# pedalier.net
KiCad netlist of a schematic drawn in EAGLE
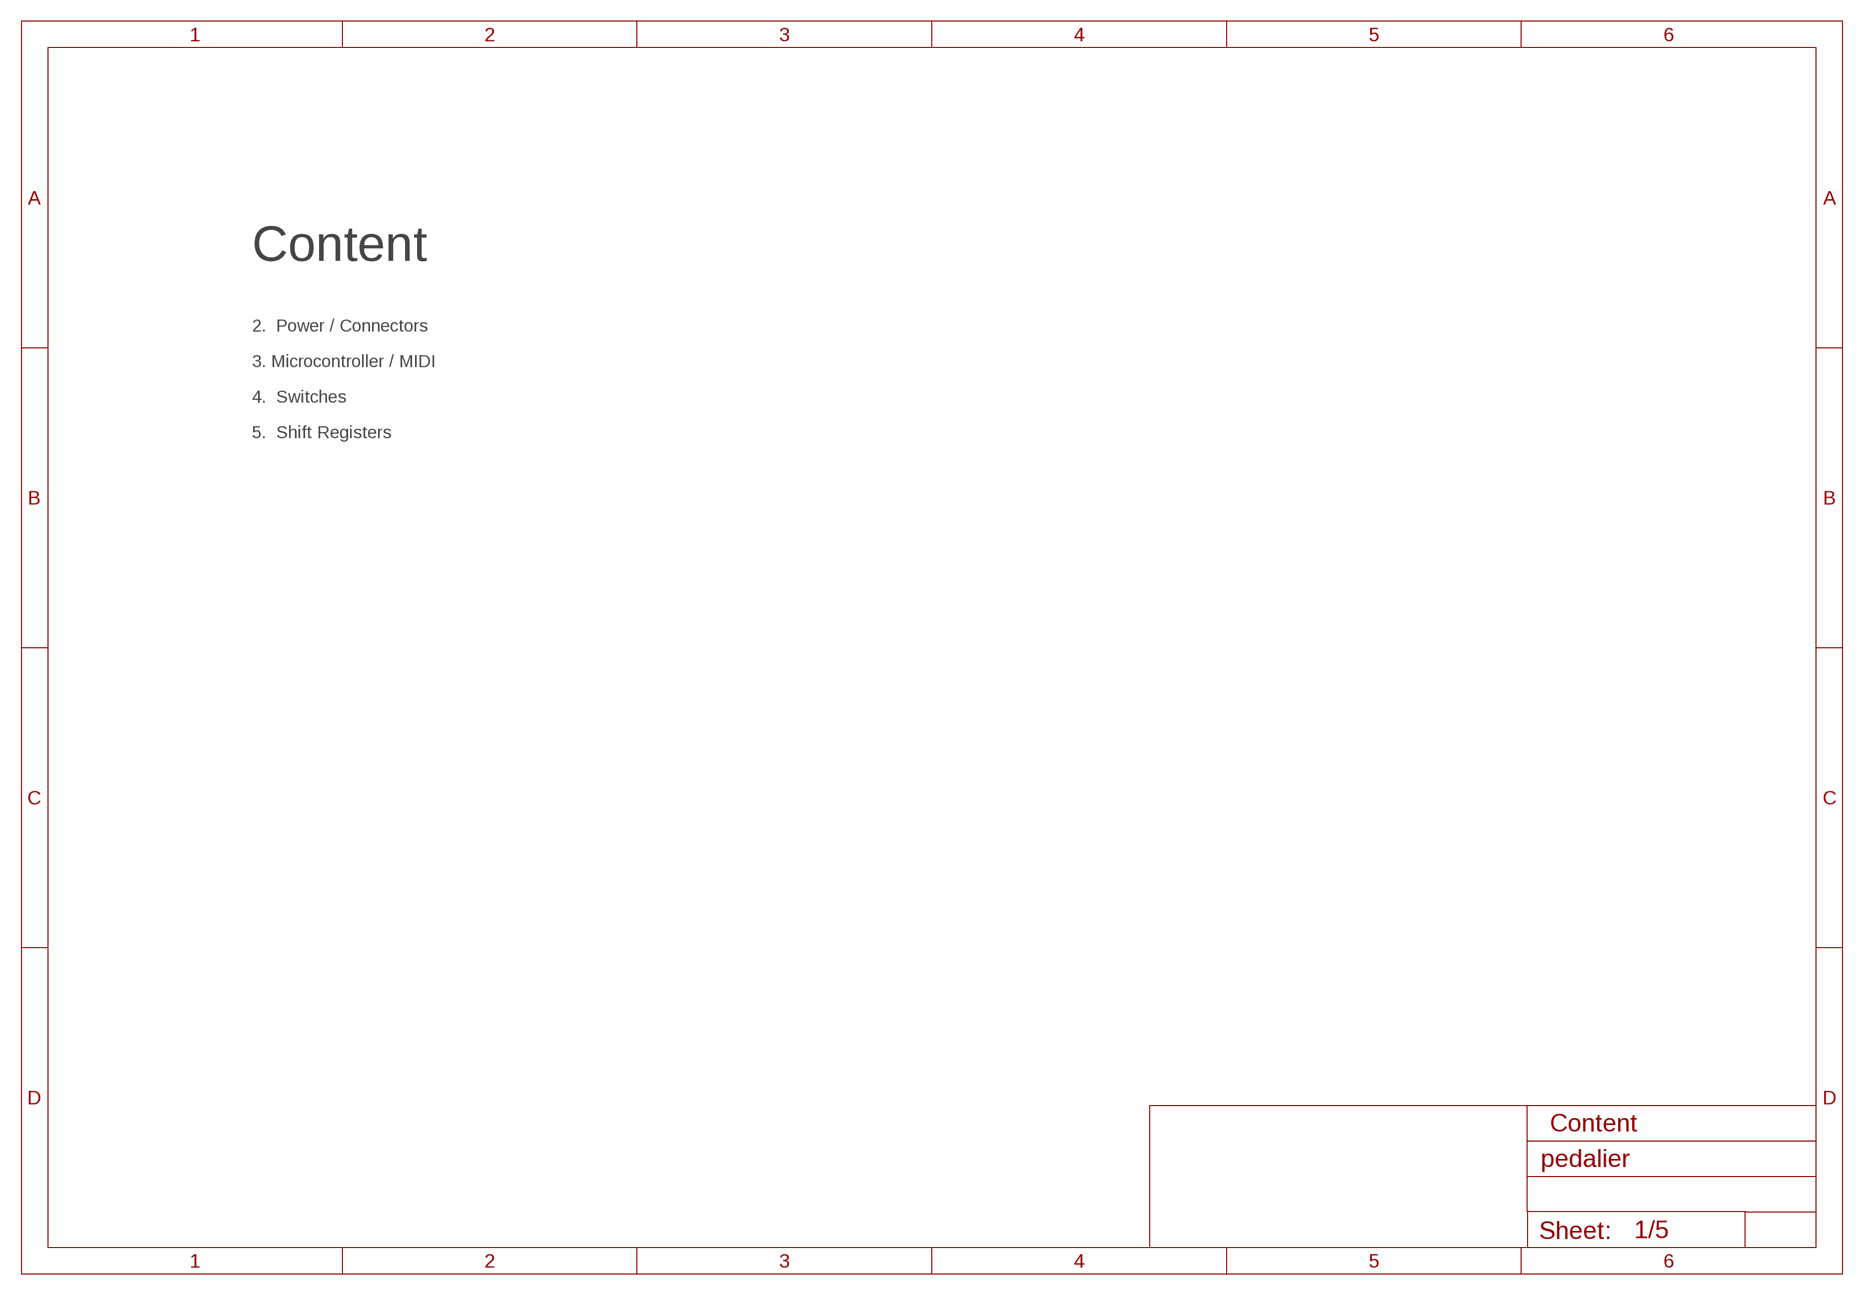
[diagram p0: schematic, sheet 1]
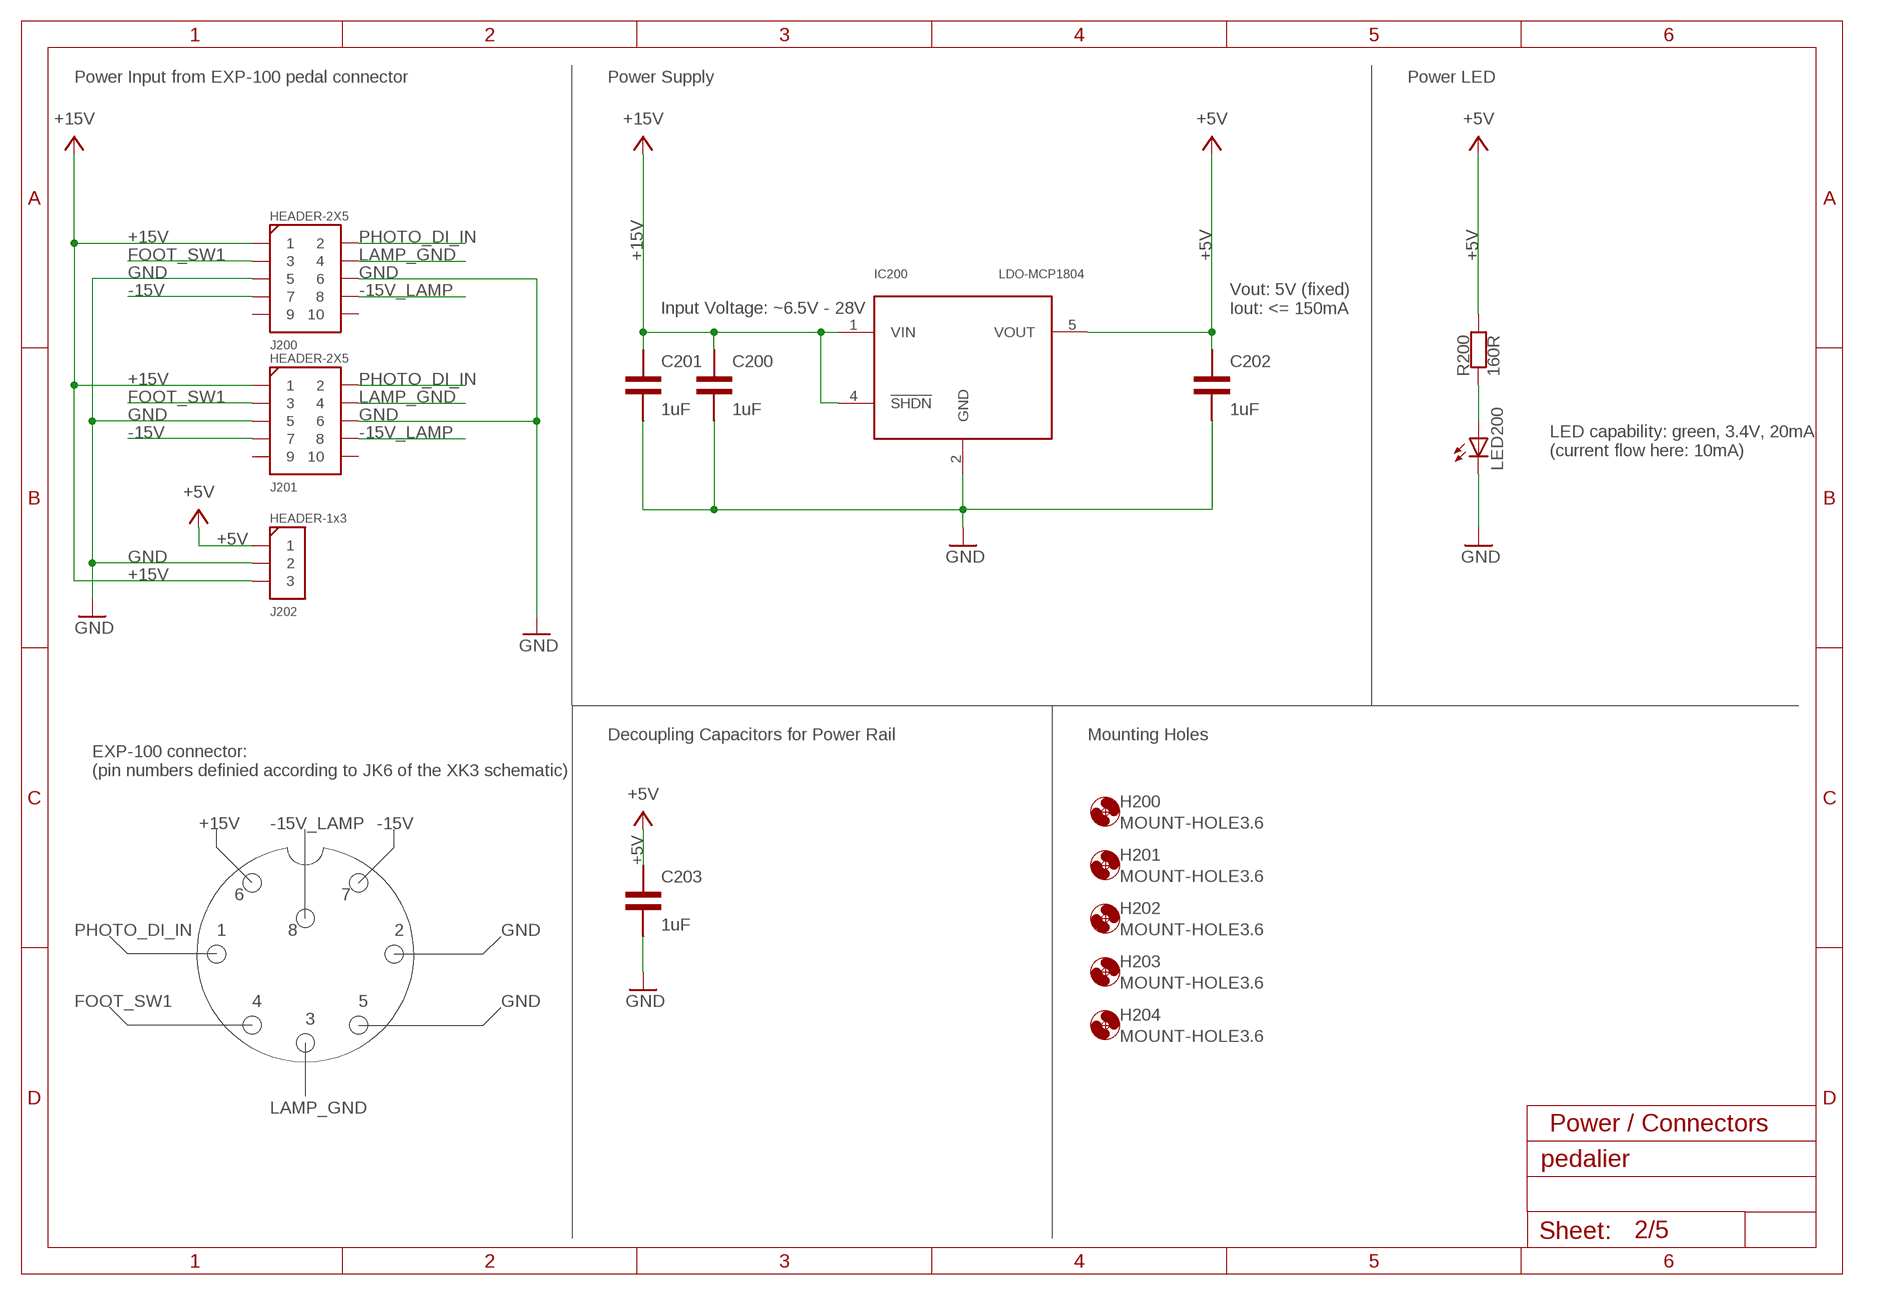
[diagram p1: schematic, sheet 2]
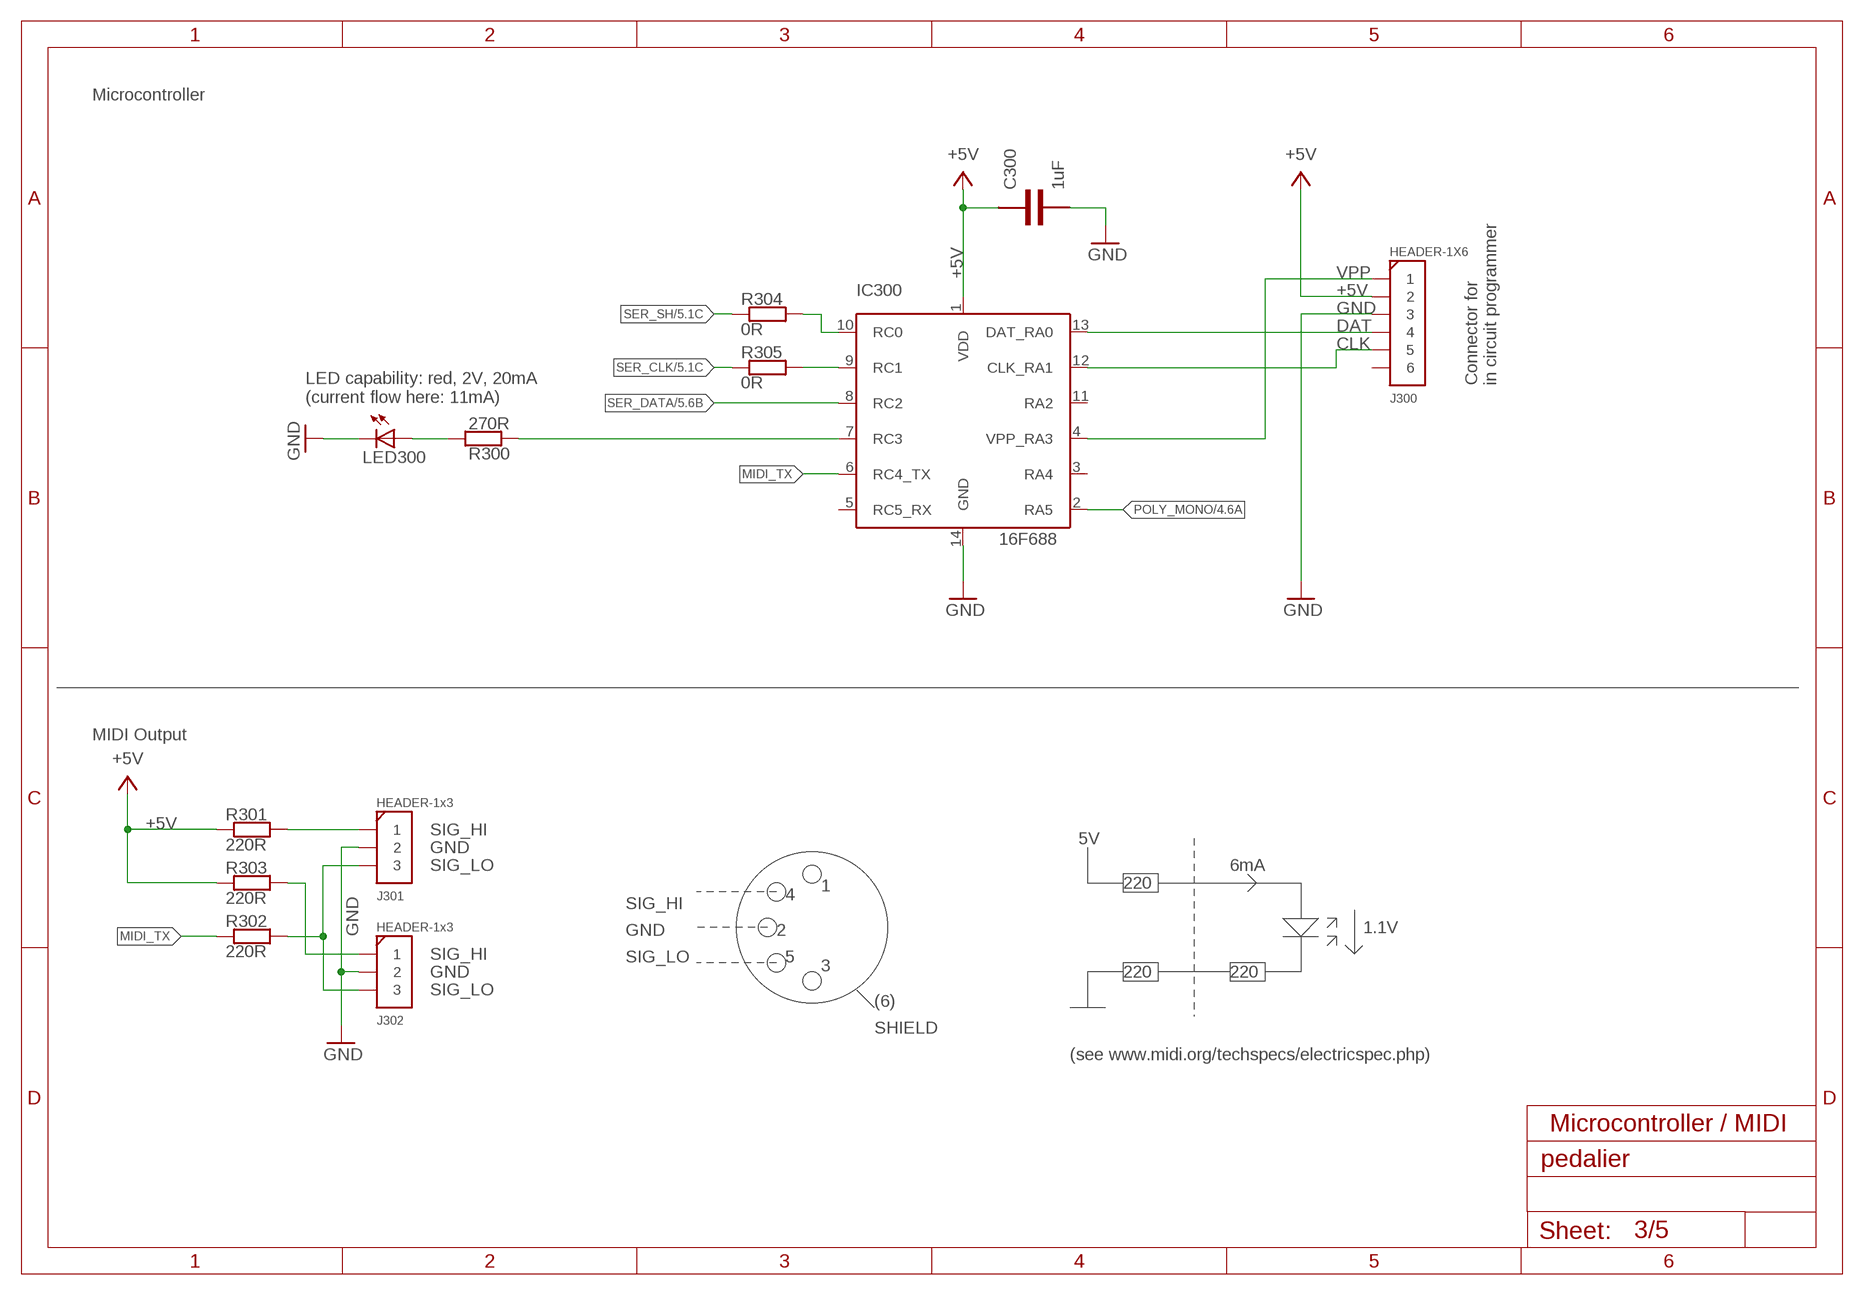
[diagram p2: schematic, sheet 3]
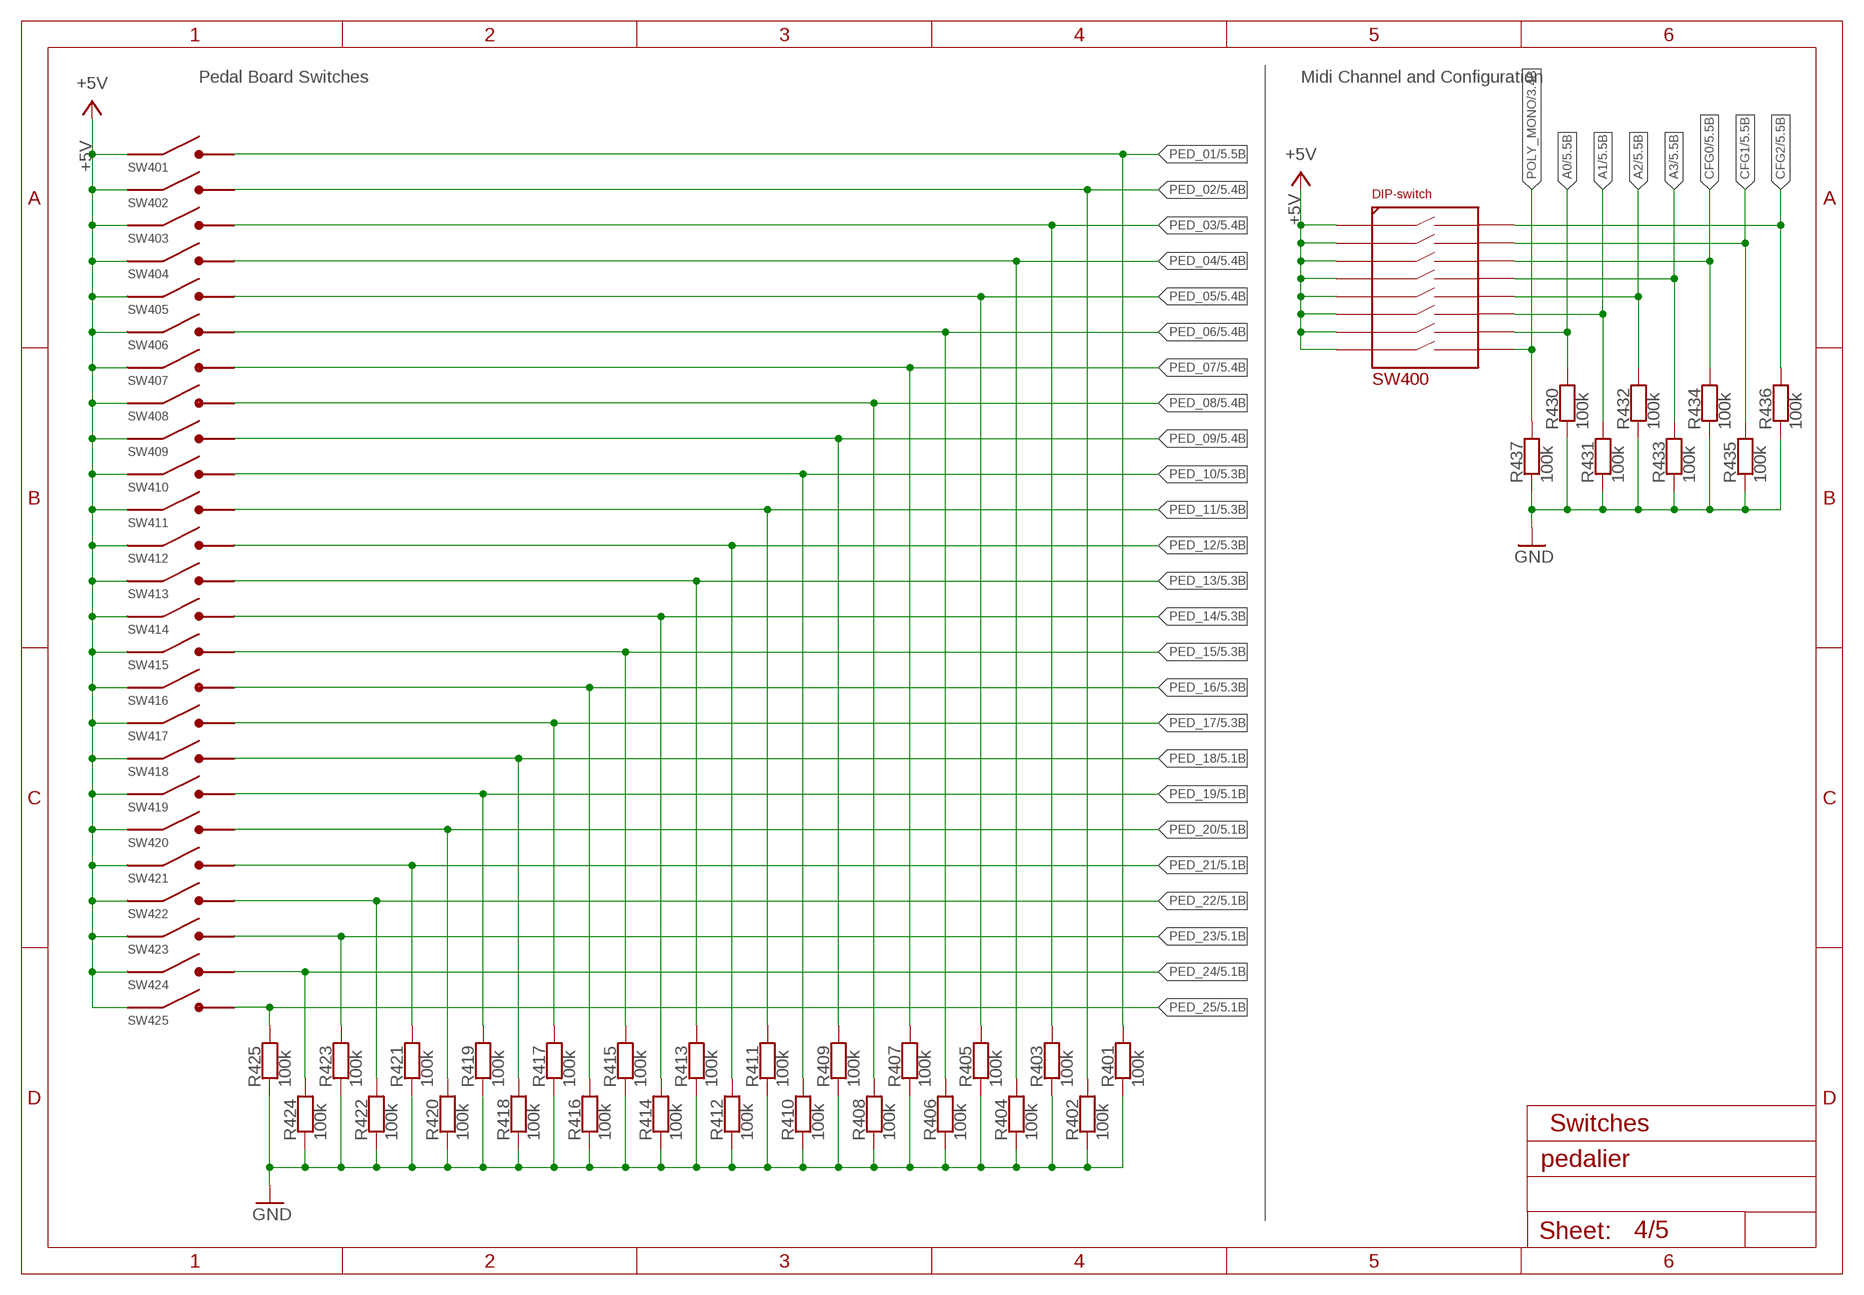
[diagram p3: schematic, sheet 4]
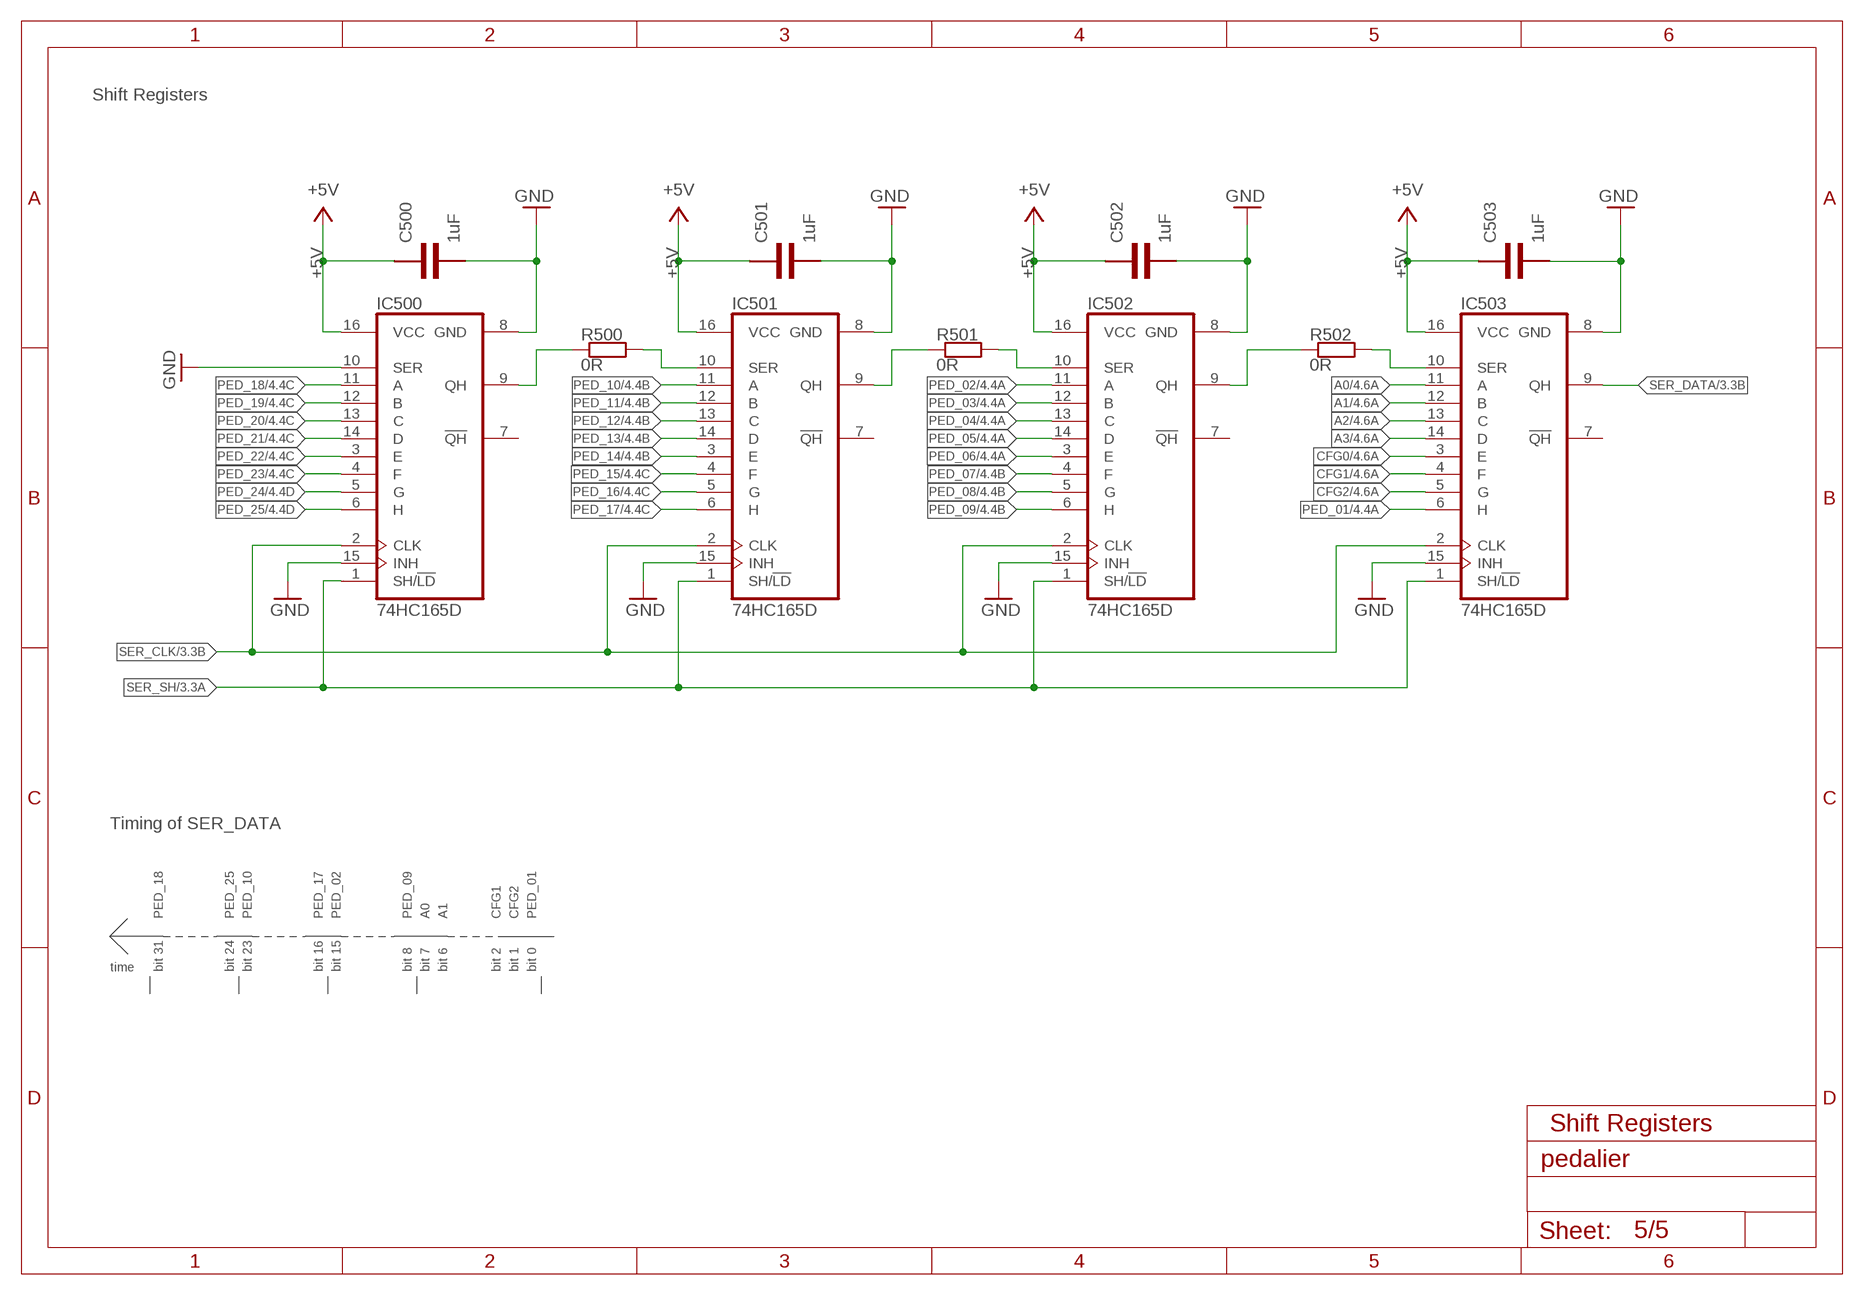
[diagram p4: schematic, sheet 5]

(export (version "E")
  (design (tool "Eeschema 10.0.6"))
  (components
    (comp (ref "R401")
      (value "100k")
      (footprint "eagle-import:R1206")
      (libsource (lib "eagle-import") (part "R"))
    )
    (comp (ref "R402")
      (value "100k")
      (footprint "eagle-import:R1206")
      (libsource (lib "eagle-import") (part "R"))
    )
    (comp (ref "R403")
      (value "100k")
      (footprint "eagle-import:R1206")
      (libsource (lib "eagle-import") (part "R"))
    )
    (comp (ref "R404")
      (value "100k")
      (footprint "eagle-import:R1206")
      (libsource (lib "eagle-import") (part "R"))
    )
    (comp (ref "R405")
      (value "100k")
      (footprint "eagle-import:R1206")
      (libsource (lib "eagle-import") (part "R"))
    )
    (comp (ref "R406")
      (value "100k")
      (footprint "eagle-import:R1206")
      (libsource (lib "eagle-import") (part "R"))
    )
    (comp (ref "R407")
      (value "100k")
      (footprint "eagle-import:R1206")
      (libsource (lib "eagle-import") (part "R"))
    )
    (comp (ref "R408")
      (value "100k")
      (footprint "eagle-import:R1206")
      (libsource (lib "eagle-import") (part "R"))
    )
    (comp (ref "R409")
      (value "100k")
      (footprint "eagle-import:R1206")
      (libsource (lib "eagle-import") (part "R"))
    )
    (comp (ref "R410")
      (value "100k")
      (footprint "eagle-import:R1206")
      (libsource (lib "eagle-import") (part "R"))
    )
    (comp (ref "R411")
      (value "100k")
      (footprint "eagle-import:R1206")
      (libsource (lib "eagle-import") (part "R"))
    )
    (comp (ref "R412")
      (value "100k")
      (footprint "eagle-import:R1206")
      (libsource (lib "eagle-import") (part "R"))
    )
    (comp (ref "R413")
      (value "100k")
      (footprint "eagle-import:R1206")
      (libsource (lib "eagle-import") (part "R"))
    )
    (comp (ref "R414")
      (value "100k")
      (footprint "eagle-import:R1206")
      (libsource (lib "eagle-import") (part "R"))
    )
    (comp (ref "R415")
      (value "100k")
      (footprint "eagle-import:R1206")
      (libsource (lib "eagle-import") (part "R"))
    )
    (comp (ref "R416")
      (value "100k")
      (footprint "eagle-import:R1206")
      (libsource (lib "eagle-import") (part "R"))
    )
    (comp (ref "R417")
      (value "100k")
      (footprint "eagle-import:R1206")
      (libsource (lib "eagle-import") (part "R"))
    )
    (comp (ref "R418")
      (value "100k")
      (footprint "eagle-import:R1206")
      (libsource (lib "eagle-import") (part "R"))
    )
    (comp (ref "R419")
      (value "100k")
      (footprint "eagle-import:R1206")
      (libsource (lib "eagle-import") (part "R"))
    )
    (comp (ref "R420")
      (value "100k")
      (footprint "eagle-import:R1206")
      (libsource (lib "eagle-import") (part "R"))
    )
    (comp (ref "R421")
      (value "100k")
      (footprint "eagle-import:R1206")
      (libsource (lib "eagle-import") (part "R"))
    )
    (comp (ref "R422")
      (value "100k")
      (footprint "eagle-import:R1206")
      (libsource (lib "eagle-import") (part "R"))
    )
    (comp (ref "R423")
      (value "100k")
      (footprint "eagle-import:R1206")
      (libsource (lib "eagle-import") (part "R"))
    )
    (comp (ref "R424")
      (value "100k")
      (footprint "eagle-import:R1206")
      (libsource (lib "eagle-import") (part "R"))
    )
    (comp (ref "R425")
      (value "100k")
      (footprint "eagle-import:R1206")
      (libsource (lib "eagle-import") (part "R"))
    )
    (comp (ref "R430")
      (value "100k")
      (footprint "eagle-import:R1206")
      (libsource (lib "eagle-import") (part "R"))
    )
    (comp (ref "R431")
      (value "100k")
      (footprint "eagle-import:R1206")
      (libsource (lib "eagle-import") (part "R"))
    )
    (comp (ref "R432")
      (value "100k")
      (footprint "eagle-import:R1206")
      (libsource (lib "eagle-import") (part "R"))
    )
    (comp (ref "R433")
      (value "100k")
      (footprint "eagle-import:R1206")
      (libsource (lib "eagle-import") (part "R"))
    )
    (comp (ref "R434")
      (value "100k")
      (footprint "eagle-import:R1206")
      (libsource (lib "eagle-import") (part "R"))
    )
    (comp (ref "R435")
      (value "100k")
      (footprint "eagle-import:R1206")
      (libsource (lib "eagle-import") (part "R"))
    )
    (comp (ref "R436")
      (value "100k")
      (footprint "eagle-import:R1206")
      (libsource (lib "eagle-import") (part "R"))
    )
    (comp (ref "R437")
      (value "100k")
      (footprint "eagle-import:R1206")
      (libsource (lib "eagle-import") (part "R"))
    )
    (comp (ref "SW400")
      (value "DIP-SW-8X")
      (footprint "eagle-import:DIP-SW-8X-GULLWING")
      (libsource (lib "eagle-import") (part "DIP-SW-8X"))
    )
    (comp (ref "SW401")
      (value "REED-SW")
      (footprint "eagle-import:KSK-1A35-SMD")
      (libsource (lib "eagle-import") (part "REED-SW"))
    )
    (comp (ref "SW402")
      (value "REED-SW")
      (footprint "eagle-import:KSK-1A35-SMD")
      (libsource (lib "eagle-import") (part "REED-SW"))
    )
    (comp (ref "SW403")
      (value "REED-SW")
      (footprint "eagle-import:KSK-1A35-SMD")
      (libsource (lib "eagle-import") (part "REED-SW"))
    )
    (comp (ref "SW404")
      (value "REED-SW")
      (footprint "eagle-import:KSK-1A35-SMD")
      (libsource (lib "eagle-import") (part "REED-SW"))
    )
    (comp (ref "SW405")
      (value "REED-SW")
      (footprint "eagle-import:KSK-1A35-SMD")
      (libsource (lib "eagle-import") (part "REED-SW"))
    )
    (comp (ref "SW406")
      (value "REED-SW")
      (footprint "eagle-import:KSK-1A35-SMD")
      (libsource (lib "eagle-import") (part "REED-SW"))
    )
    (comp (ref "SW407")
      (value "REED-SW")
      (footprint "eagle-import:KSK-1A35-SMD")
      (libsource (lib "eagle-import") (part "REED-SW"))
    )
    (comp (ref "SW408")
      (value "REED-SW")
      (footprint "eagle-import:KSK-1A35-SMD")
      (libsource (lib "eagle-import") (part "REED-SW"))
    )
    (comp (ref "SW409")
      (value "REED-SW")
      (footprint "eagle-import:KSK-1A35-SMD")
      (libsource (lib "eagle-import") (part "REED-SW"))
    )
    (comp (ref "SW410")
      (value "REED-SW")
      (footprint "eagle-import:KSK-1A35-SMD")
      (libsource (lib "eagle-import") (part "REED-SW"))
    )
    (comp (ref "SW411")
      (value "REED-SW")
      (footprint "eagle-import:KSK-1A35-SMD")
      (libsource (lib "eagle-import") (part "REED-SW"))
    )
    (comp (ref "SW412")
      (value "REED-SW")
      (footprint "eagle-import:KSK-1A35-SMD")
      (libsource (lib "eagle-import") (part "REED-SW"))
    )
    (comp (ref "SW413")
      (value "REED-SW")
      (footprint "eagle-import:KSK-1A35-SMD")
      (libsource (lib "eagle-import") (part "REED-SW"))
    )
    (comp (ref "SW414")
      (value "REED-SW")
      (footprint "eagle-import:KSK-1A35-SMD")
      (libsource (lib "eagle-import") (part "REED-SW"))
    )
    (comp (ref "SW415")
      (value "REED-SW")
      (footprint "eagle-import:KSK-1A35-SMD")
      (libsource (lib "eagle-import") (part "REED-SW"))
    )
    (comp (ref "SW416")
      (value "REED-SW")
      (footprint "eagle-import:KSK-1A35-SMD")
      (libsource (lib "eagle-import") (part "REED-SW"))
    )
    (comp (ref "SW417")
      (value "REED-SW")
      (footprint "eagle-import:KSK-1A35-SMD")
      (libsource (lib "eagle-import") (part "REED-SW"))
    )
    (comp (ref "SW418")
      (value "REED-SW")
      (footprint "eagle-import:KSK-1A35-SMD")
      (libsource (lib "eagle-import") (part "REED-SW"))
    )
    (comp (ref "SW419")
      (value "REED-SW")
      (footprint "eagle-import:KSK-1A35-SMD")
      (libsource (lib "eagle-import") (part "REED-SW"))
    )
    (comp (ref "SW420")
      (value "REED-SW")
      (footprint "eagle-import:KSK-1A35-SMD")
      (libsource (lib "eagle-import") (part "REED-SW"))
    )
    (comp (ref "SW421")
      (value "REED-SW")
      (footprint "eagle-import:KSK-1A35-SMD")
      (libsource (lib "eagle-import") (part "REED-SW"))
    )
    (comp (ref "SW422")
      (value "REED-SW")
      (footprint "eagle-import:KSK-1A35-SMD")
      (libsource (lib "eagle-import") (part "REED-SW"))
    )
    (comp (ref "SW423")
      (value "REED-SW")
      (footprint "eagle-import:KSK-1A35-SMD")
      (libsource (lib "eagle-import") (part "REED-SW"))
    )
    (comp (ref "SW424")
      (value "REED-SW")
      (footprint "eagle-import:KSK-1A35-SMD")
      (libsource (lib "eagle-import") (part "REED-SW"))
    )
    (comp (ref "SW425")
      (value "REED-SW")
      (footprint "eagle-import:KSK-1A35-SMD")
      (libsource (lib "eagle-import") (part "REED-SW"))
    )
    (comp (ref "C200")
      (value "1uF")
      (footprint "eagle-import:C1206")
      (libsource (lib "eagle-import") (part "C"))
    )
    (comp (ref "C201")
      (value "1uF")
      (footprint "eagle-import:C1206")
      (libsource (lib "eagle-import") (part "C"))
    )
    (comp (ref "C202")
      (value "1uF")
      (footprint "eagle-import:C1206")
      (libsource (lib "eagle-import") (part "C"))
    )
    (comp (ref "C203")
      (value "1uF")
      (footprint "eagle-import:C1206")
      (libsource (lib "eagle-import") (part "C"))
    )
    (comp (ref "H200")
      (value "MOUNT-HOLE3.6")
      (footprint "eagle-import:3,6")
      (libsource (lib "eagle-import") (part "MOUNT-HOLE3.6"))
    )
    (comp (ref "H201")
      (value "MOUNT-HOLE3.6")
      (footprint "eagle-import:3,6")
      (libsource (lib "eagle-import") (part "MOUNT-HOLE3.6"))
    )
    (comp (ref "H202")
      (value "MOUNT-HOLE3.6")
      (footprint "eagle-import:3,6")
      (libsource (lib "eagle-import") (part "MOUNT-HOLE3.6"))
    )
    (comp (ref "H203")
      (value "MOUNT-HOLE3.6")
      (footprint "eagle-import:3,6")
      (libsource (lib "eagle-import") (part "MOUNT-HOLE3.6"))
    )
    (comp (ref "H204")
      (value "MOUNT-HOLE3.6")
      (footprint "eagle-import:3,6")
      (libsource (lib "eagle-import") (part "MOUNT-HOLE3.6"))
    )
    (comp (ref "IC200")
      (value "LDO-MCP1804")
      (footprint "eagle-import:SOT23-5")
      (libsource (lib "eagle-import") (part "LDO-MCP1804"))
    )
    (comp (ref "J200")
      (value "HEADER-2X5")
      (footprint "eagle-import:HEADER-2X5")
      (libsource (lib "eagle-import") (part "HEADER-2X5"))
    )
    (comp (ref "J201")
      (value "HEADER-2X5")
      (footprint "eagle-import:HEADER-2X5")
      (libsource (lib "eagle-import") (part "HEADER-2X5"))
    )
    (comp (ref "J202")
      (value "HEADER-1X3")
      (footprint "eagle-import:HEADER-1X3")
      (libsource (lib "eagle-import") (part "HEADER-1X3"))
    )
    (comp (ref "LED200")
      (value "LED-BRIGHTEK")
      (footprint "eagle-import:LED1206")
      (libsource (lib "eagle-import") (part "LED-BRIGHTEK"))
    )
    (comp (ref "R200")
      (value "160R")
      (footprint "eagle-import:R1206")
      (libsource (lib "eagle-import") (part "R"))
    )
    (comp (ref "C300")
      (value "1uF")
      (footprint "eagle-import:C1206")
      (libsource (lib "eagle-import") (part "C"))
    )
    (comp (ref "IC300")
      (value "PIC16F688SOIC14")
      (footprint "eagle-import:SO14")
      (libsource (lib "eagle-import") (part "PIC16F688SOIC14"))
    )
    (comp (ref "J300")
      (value "HEADER-1X6")
      (footprint "eagle-import:HEADER-1X6")
      (libsource (lib "eagle-import") (part "HEADER-1X6"))
    )
    (comp (ref "J301")
      (value "HEADER-1X3")
      (footprint "eagle-import:HEADER-1X3")
      (libsource (lib "eagle-import") (part "HEADER-1X3"))
    )
    (comp (ref "J302")
      (value "HEADER-1X3")
      (footprint "eagle-import:HEADER-1X3")
      (libsource (lib "eagle-import") (part "HEADER-1X3"))
    )
    (comp (ref "LED300")
      (value "LED-BRIGHTEK")
      (footprint "eagle-import:LED1206")
      (libsource (lib "eagle-import") (part "LED-BRIGHTEK"))
    )
    (comp (ref "R300")
      (value "270R")
      (footprint "eagle-import:R1206")
      (libsource (lib "eagle-import") (part "R"))
    )
    (comp (ref "R301")
      (value "220R")
      (footprint "eagle-import:R1206")
      (libsource (lib "eagle-import") (part "R"))
    )
    (comp (ref "R302")
      (value "220R")
      (footprint "eagle-import:R1206")
      (libsource (lib "eagle-import") (part "R"))
    )
    (comp (ref "R303")
      (value "220R")
      (footprint "eagle-import:R1206")
      (libsource (lib "eagle-import") (part "R"))
    )
    (comp (ref "R304")
      (value "0R")
      (footprint "eagle-import:R1206")
      (libsource (lib "eagle-import") (part "R"))
    )
    (comp (ref "R305")
      (value "0R")
      (footprint "eagle-import:R1206")
      (libsource (lib "eagle-import") (part "R"))
    )
    (comp (ref "C500")
      (value "1uF")
      (footprint "eagle-import:C1206")
      (libsource (lib "eagle-import") (part "C"))
    )
    (comp (ref "C501")
      (value "1uF")
      (footprint "eagle-import:C1206")
      (libsource (lib "eagle-import") (part "C"))
    )
    (comp (ref "C502")
      (value "1uF")
      (footprint "eagle-import:C1206")
      (libsource (lib "eagle-import") (part "C"))
    )
    (comp (ref "C503")
      (value "1uF")
      (footprint "eagle-import:C1206")
      (libsource (lib "eagle-import") (part "C"))
    )
    (comp (ref "IC500")
      (value "74HC165D")
      (footprint "eagle-import:SO16")
      (libsource (lib "eagle-import") (part "74HC165D"))
    )
    (comp (ref "IC501")
      (value "74HC165D")
      (footprint "eagle-import:SO16")
      (libsource (lib "eagle-import") (part "74HC165D"))
    )
    (comp (ref "IC502")
      (value "74HC165D")
      (footprint "eagle-import:SO16")
      (libsource (lib "eagle-import") (part "74HC165D"))
    )
    (comp (ref "IC503")
      (value "74HC165D")
      (footprint "eagle-import:SO16")
      (libsource (lib "eagle-import") (part "74HC165D"))
    )
    (comp (ref "R500")
      (value "0R")
      (footprint "eagle-import:R1206")
      (libsource (lib "eagle-import") (part "R"))
    )
    (comp (ref "R501")
      (value "0R")
      (footprint "eagle-import:R1206")
      (libsource (lib "eagle-import") (part "R"))
    )
    (comp (ref "R502")
      (value "0R")
      (footprint "eagle-import:R1206")
      (libsource (lib "eagle-import") (part "R"))
    )
  )
  (nets
    (net (code "1") (name "+5V") (class "Default")
      (node (ref "C202") (pin "1") (pinfunction "P$1_1") (pintype "bidirectional"))
      (node (ref "C203") (pin "1") (pinfunction "P$1_1") (pintype "bidirectional"))
      (node (ref "C300") (pin "1") (pinfunction "P$1_1") (pintype "bidirectional"))
      (node (ref "C500") (pin "1") (pinfunction "P$1_1") (pintype "bidirectional"))
      (node (ref "C501") (pin "1") (pinfunction "P$1_1") (pintype "bidirectional"))
      (node (ref "C502") (pin "1") (pinfunction "P$1_1") (pintype "bidirectional"))
      (node (ref "C503") (pin "1") (pinfunction "P$1_1") (pintype "bidirectional"))
      (node (ref "IC200") (pin "5") (pinfunction "VOUT_5") (pintype "bidirectional"))
      (node (ref "IC300") (pin "1") (pinfunction "VDD_1") (pintype "passive"))
      (node (ref "IC500") (pin "16") (pinfunction "VCC_16") (pintype "bidirectional"))
      (node (ref "IC501") (pin "16") (pinfunction "VCC_16") (pintype "bidirectional"))
      (node (ref "IC502") (pin "16") (pinfunction "VCC_16") (pintype "bidirectional"))
      (node (ref "IC503") (pin "16") (pinfunction "VCC_16") (pintype "bidirectional"))
      (node (ref "J202") (pin "P$1") (pinfunction "1_P$1") (pintype "bidirectional"))
      (node (ref "J300") (pin "P$2") (pinfunction "2_P$2") (pintype "bidirectional"))
      (node (ref "R200") (pin "2") (pinfunction "P$2_2") (pintype "bidirectional"))
      (node (ref "R301") (pin "1") (pinfunction "P$1_1") (pintype "bidirectional"))
      (node (ref "R303") (pin "1") (pinfunction "P$1_1") (pintype "bidirectional"))
      (node (ref "SW400") (pin "P$1") (pinfunction "P$1_P$1") (pintype "bidirectional"))
      (node (ref "SW400") (pin "P$11") (pinfunction "P$11_P$11") (pintype "bidirectional"))
      (node (ref "SW400") (pin "P$13") (pinfunction "P$13_P$13") (pintype "bidirectional"))
      (node (ref "SW400") (pin "P$15") (pinfunction "P$15_P$15") (pintype "bidirectional"))
      (node (ref "SW400") (pin "P$3") (pinfunction "P$3_P$3") (pintype "bidirectional"))
      (node (ref "SW400") (pin "P$5") (pinfunction "P$5_P$5") (pintype "bidirectional"))
      (node (ref "SW400") (pin "P$7") (pinfunction "P$7_P$7") (pintype "bidirectional"))
      (node (ref "SW400") (pin "P$9") (pinfunction "P$9_P$9") (pintype "bidirectional"))
      (node (ref "SW401") (pin "1") (pinfunction "1_1") (pintype "bidirectional"))
      (node (ref "SW402") (pin "1") (pinfunction "1_1") (pintype "bidirectional"))
      (node (ref "SW403") (pin "1") (pinfunction "1_1") (pintype "bidirectional"))
      (node (ref "SW404") (pin "1") (pinfunction "1_1") (pintype "bidirectional"))
      (node (ref "SW405") (pin "1") (pinfunction "1_1") (pintype "bidirectional"))
      (node (ref "SW406") (pin "1") (pinfunction "1_1") (pintype "bidirectional"))
      (node (ref "SW407") (pin "1") (pinfunction "1_1") (pintype "bidirectional"))
      (node (ref "SW408") (pin "1") (pinfunction "1_1") (pintype "bidirectional"))
      (node (ref "SW409") (pin "1") (pinfunction "1_1") (pintype "bidirectional"))
      (node (ref "SW410") (pin "1") (pinfunction "1_1") (pintype "bidirectional"))
      (node (ref "SW411") (pin "1") (pinfunction "1_1") (pintype "bidirectional"))
      (node (ref "SW412") (pin "1") (pinfunction "1_1") (pintype "bidirectional"))
      (node (ref "SW413") (pin "1") (pinfunction "1_1") (pintype "bidirectional"))
      (node (ref "SW414") (pin "1") (pinfunction "1_1") (pintype "bidirectional"))
      (node (ref "SW415") (pin "1") (pinfunction "1_1") (pintype "bidirectional"))
      (node (ref "SW416") (pin "1") (pinfunction "1_1") (pintype "bidirectional"))
      (node (ref "SW417") (pin "1") (pinfunction "1_1") (pintype "bidirectional"))
      (node (ref "SW418") (pin "1") (pinfunction "1_1") (pintype "bidirectional"))
      (node (ref "SW419") (pin "1") (pinfunction "1_1") (pintype "bidirectional"))
      (node (ref "SW420") (pin "1") (pinfunction "1_1") (pintype "bidirectional"))
      (node (ref "SW421") (pin "1") (pinfunction "1_1") (pintype "bidirectional"))
      (node (ref "SW422") (pin "1") (pinfunction "1_1") (pintype "bidirectional"))
      (node (ref "SW423") (pin "1") (pinfunction "1_1") (pintype "bidirectional"))
      (node (ref "SW424") (pin "1") (pinfunction "1_1") (pintype "bidirectional"))
      (node (ref "SW425") (pin "1") (pinfunction "1_1") (pintype "bidirectional"))
    )
    (net (code "2") (name "+15V") (class "Default")
      (node (ref "C200") (pin "1") (pinfunction "P$1_1") (pintype "bidirectional"))
      (node (ref "C201") (pin "1") (pinfunction "P$1_1") (pintype "bidirectional"))
      (node (ref "IC200") (pin "1") (pinfunction "VIN_1") (pintype "bidirectional"))
      (node (ref "IC200") (pin "4") (pinfunction "~{SHDN}_4") (pintype "bidirectional"))
      (node (ref "J200") (pin "P$1") (pinfunction "1_P$1") (pintype "bidirectional"))
      (node (ref "J201") (pin "P$1") (pinfunction "1_P$1") (pintype "bidirectional"))
      (node (ref "J202") (pin "P$3") (pinfunction "3_P$3") (pintype "bidirectional"))
    )
    (net (code "3") (name "-15V") (class "Default")
      (node (ref "J200") (pin "P$7") (pinfunction "7_P$7") (pintype "bidirectional"))
      (node (ref "J201") (pin "P$7") (pinfunction "7_P$7") (pintype "bidirectional"))
    )
    (net (code "4") (name "-15V_LAMP") (class "Default")
      (node (ref "J200") (pin "P$8") (pinfunction "8_P$8") (pintype "bidirectional"))
      (node (ref "J201") (pin "P$8") (pinfunction "8_P$8") (pintype "bidirectional"))
    )
    (net (code "5") (name "A0") (class "Default")
      (node (ref "IC503") (pin "11") (pinfunction "A_11") (pintype "input"))
      (node (ref "R430") (pin "2") (pinfunction "P$2_2") (pintype "bidirectional"))
      (node (ref "SW400") (pin "P$14") (pinfunction "P$14_P$14") (pintype "bidirectional"))
    )
    (net (code "6") (name "A1") (class "Default")
      (node (ref "IC503") (pin "12") (pinfunction "B_12") (pintype "input"))
      (node (ref "R431") (pin "2") (pinfunction "P$2_2") (pintype "bidirectional"))
      (node (ref "SW400") (pin "P$12") (pinfunction "P$12_P$12") (pintype "bidirectional"))
    )
    (net (code "7") (name "A2") (class "Default")
      (node (ref "IC503") (pin "13") (pinfunction "C_13") (pintype "input"))
      (node (ref "R432") (pin "2") (pinfunction "P$2_2") (pintype "bidirectional"))
      (node (ref "SW400") (pin "P$10") (pinfunction "P$10_P$10") (pintype "bidirectional"))
    )
    (net (code "8") (name "A3") (class "Default")
      (node (ref "IC503") (pin "14") (pinfunction "D_14") (pintype "input"))
      (node (ref "R433") (pin "2") (pinfunction "P$2_2") (pintype "bidirectional"))
      (node (ref "SW400") (pin "P$8") (pinfunction "P$8_P$8") (pintype "bidirectional"))
    )
    (net (code "9") (name "CFG0") (class "Default")
      (node (ref "IC503") (pin "3") (pinfunction "E_3") (pintype "input"))
      (node (ref "R434") (pin "2") (pinfunction "P$2_2") (pintype "bidirectional"))
      (node (ref "SW400") (pin "P$6") (pinfunction "P$6_P$6") (pintype "bidirectional"))
    )
    (net (code "10") (name "CFG1") (class "Default")
      (node (ref "IC503") (pin "4") (pinfunction "F_4") (pintype "input"))
      (node (ref "R435") (pin "2") (pinfunction "P$2_2") (pintype "bidirectional"))
      (node (ref "SW400") (pin "P$4") (pinfunction "P$4_P$4") (pintype "bidirectional"))
    )
    (net (code "11") (name "CFG2") (class "Default")
      (node (ref "IC503") (pin "5") (pinfunction "G_5") (pintype "input"))
      (node (ref "R436") (pin "2") (pinfunction "P$2_2") (pintype "bidirectional"))
      (node (ref "SW400") (pin "P$2") (pinfunction "P$2_P$2") (pintype "bidirectional"))
    )
    (net (code "12") (name "CLK") (class "Default")
      (node (ref "IC300") (pin "12") (pinfunction "CLK_RA1_12") (pintype "passive"))
      (node (ref "J300") (pin "P$5") (pinfunction "5_P$5") (pintype "bidirectional"))
    )
    (net (code "13") (name "DAT") (class "Default")
      (node (ref "IC300") (pin "13") (pinfunction "DAT_RA0_13") (pintype "passive"))
      (node (ref "J300") (pin "P$4") (pinfunction "4_P$4") (pintype "bidirectional"))
    )
    (net (code "14") (name "FOOT_SW1") (class "Default")
      (node (ref "J200") (pin "P$3") (pinfunction "3_P$3") (pintype "bidirectional"))
      (node (ref "J201") (pin "P$3") (pinfunction "3_P$3") (pintype "bidirectional"))
    )
    (net (code "15") (name "GND") (class "Default")
      (node (ref "C200") (pin "2") (pinfunction "P$2_2") (pintype "bidirectional"))
      (node (ref "C201") (pin "2") (pinfunction "P$2_2") (pintype "bidirectional"))
      (node (ref "C202") (pin "2") (pinfunction "P$2_2") (pintype "bidirectional"))
      (node (ref "C203") (pin "2") (pinfunction "P$2_2") (pintype "bidirectional"))
      (node (ref "C300") (pin "2") (pinfunction "P$2_2") (pintype "bidirectional"))
      (node (ref "C500") (pin "2") (pinfunction "P$2_2") (pintype "bidirectional"))
      (node (ref "C501") (pin "2") (pinfunction "P$2_2") (pintype "bidirectional"))
      (node (ref "C502") (pin "2") (pinfunction "P$2_2") (pintype "bidirectional"))
      (node (ref "C503") (pin "2") (pinfunction "P$2_2") (pintype "bidirectional"))
      (node (ref "IC200") (pin "2") (pinfunction "GND_2") (pintype "bidirectional"))
      (node (ref "IC300") (pin "14") (pinfunction "GND_14") (pintype "passive"))
      (node (ref "IC500") (pin "10") (pinfunction "SER_10") (pintype "input"))
      (node (ref "IC500") (pin "15") (pinfunction "INH_15") (pintype "input"))
      (node (ref "IC500") (pin "8") (pinfunction "GND_8") (pintype "bidirectional"))
      (node (ref "IC501") (pin "15") (pinfunction "INH_15") (pintype "input"))
      (node (ref "IC501") (pin "8") (pinfunction "GND_8") (pintype "bidirectional"))
      (node (ref "IC502") (pin "15") (pinfunction "INH_15") (pintype "input"))
      (node (ref "IC502") (pin "8") (pinfunction "GND_8") (pintype "bidirectional"))
      (node (ref "IC503") (pin "15") (pinfunction "INH_15") (pintype "input"))
      (node (ref "IC503") (pin "8") (pinfunction "GND_8") (pintype "bidirectional"))
      (node (ref "J200") (pin "P$5") (pinfunction "5_P$5") (pintype "bidirectional"))
      (node (ref "J200") (pin "P$6") (pinfunction "6_P$6") (pintype "bidirectional"))
      (node (ref "J201") (pin "P$5") (pinfunction "5_P$5") (pintype "bidirectional"))
      (node (ref "J201") (pin "P$6") (pinfunction "6_P$6") (pintype "bidirectional"))
      (node (ref "J202") (pin "P$2") (pinfunction "2_P$2") (pintype "bidirectional"))
      (node (ref "J300") (pin "P$3") (pinfunction "3_P$3") (pintype "bidirectional"))
      (node (ref "J301") (pin "P$2") (pinfunction "2_P$2") (pintype "bidirectional"))
      (node (ref "J302") (pin "P$2") (pinfunction "2_P$2") (pintype "bidirectional"))
      (node (ref "LED200") (pin "P$1") (pinfunction "C_P$1") (pintype "passive"))
      (node (ref "LED300") (pin "P$1") (pinfunction "C_P$1") (pintype "passive"))
      (node (ref "R401") (pin "1") (pinfunction "P$1_1") (pintype "bidirectional"))
      (node (ref "R402") (pin "1") (pinfunction "P$1_1") (pintype "bidirectional"))
      (node (ref "R403") (pin "1") (pinfunction "P$1_1") (pintype "bidirectional"))
      (node (ref "R404") (pin "1") (pinfunction "P$1_1") (pintype "bidirectional"))
      (node (ref "R405") (pin "1") (pinfunction "P$1_1") (pintype "bidirectional"))
      (node (ref "R406") (pin "1") (pinfunction "P$1_1") (pintype "bidirectional"))
      (node (ref "R407") (pin "1") (pinfunction "P$1_1") (pintype "bidirectional"))
      (node (ref "R408") (pin "1") (pinfunction "P$1_1") (pintype "bidirectional"))
      (node (ref "R409") (pin "1") (pinfunction "P$1_1") (pintype "bidirectional"))
      (node (ref "R410") (pin "1") (pinfunction "P$1_1") (pintype "bidirectional"))
      (node (ref "R411") (pin "1") (pinfunction "P$1_1") (pintype "bidirectional"))
      (node (ref "R412") (pin "1") (pinfunction "P$1_1") (pintype "bidirectional"))
      (node (ref "R413") (pin "1") (pinfunction "P$1_1") (pintype "bidirectional"))
      (node (ref "R414") (pin "1") (pinfunction "P$1_1") (pintype "bidirectional"))
      (node (ref "R415") (pin "1") (pinfunction "P$1_1") (pintype "bidirectional"))
      (node (ref "R416") (pin "1") (pinfunction "P$1_1") (pintype "bidirectional"))
      (node (ref "R417") (pin "1") (pinfunction "P$1_1") (pintype "bidirectional"))
      (node (ref "R418") (pin "1") (pinfunction "P$1_1") (pintype "bidirectional"))
      (node (ref "R419") (pin "1") (pinfunction "P$1_1") (pintype "bidirectional"))
      (node (ref "R420") (pin "1") (pinfunction "P$1_1") (pintype "bidirectional"))
      (node (ref "R421") (pin "1") (pinfunction "P$1_1") (pintype "bidirectional"))
      (node (ref "R422") (pin "1") (pinfunction "P$1_1") (pintype "bidirectional"))
      (node (ref "R423") (pin "1") (pinfunction "P$1_1") (pintype "bidirectional"))
      (node (ref "R424") (pin "1") (pinfunction "P$1_1") (pintype "bidirectional"))
      (node (ref "R425") (pin "1") (pinfunction "P$1_1") (pintype "bidirectional"))
      (node (ref "R430") (pin "1") (pinfunction "P$1_1") (pintype "bidirectional"))
      (node (ref "R431") (pin "1") (pinfunction "P$1_1") (pintype "bidirectional"))
      (node (ref "R432") (pin "1") (pinfunction "P$1_1") (pintype "bidirectional"))
      (node (ref "R433") (pin "1") (pinfunction "P$1_1") (pintype "bidirectional"))
      (node (ref "R434") (pin "1") (pinfunction "P$1_1") (pintype "bidirectional"))
      (node (ref "R435") (pin "1") (pinfunction "P$1_1") (pintype "bidirectional"))
      (node (ref "R436") (pin "1") (pinfunction "P$1_1") (pintype "bidirectional"))
      (node (ref "R437") (pin "1") (pinfunction "P$1_1") (pintype "bidirectional"))
    )
    (net (code "16") (name "LAMP_GND") (class "Default")
      (node (ref "J200") (pin "P$4") (pinfunction "4_P$4") (pintype "bidirectional"))
      (node (ref "J201") (pin "P$4") (pinfunction "4_P$4") (pintype "bidirectional"))
    )
    (net (code "17") (name "MIDI_TX") (class "Default")
      (node (ref "IC300") (pin "6") (pinfunction "RC4_TX_6") (pintype "passive"))
      (node (ref "R302") (pin "1") (pinfunction "P$1_1") (pintype "bidirectional"))
    )
    (net (code "18") (name "Net-(IC300-RC0)") (class "Default")
      (node (ref "IC300") (pin "10") (pinfunction "RC0_10") (pintype "passive"))
      (node (ref "R304") (pin "2") (pinfunction "P$2_2") (pintype "bidirectional"))
    )
    (net (code "19") (name "Net-(IC300-RC1)") (class "Default")
      (node (ref "IC300") (pin "9") (pinfunction "RC1_9") (pintype "passive"))
      (node (ref "R305") (pin "2") (pinfunction "P$2_2") (pintype "bidirectional"))
    )
    (net (code "20") (name "Net-(IC300-RC3)") (class "Default")
      (node (ref "IC300") (pin "7") (pinfunction "RC3_7") (pintype "passive"))
      (node (ref "R300") (pin "1") (pinfunction "P$1_1") (pintype "bidirectional"))
    )
    (net (code "21") (name "Net-(IC500-QH)") (class "Default")
      (node (ref "IC500") (pin "9") (pinfunction "QH_9") (pintype "output"))
      (node (ref "R500") (pin "1") (pinfunction "P$1_1") (pintype "bidirectional"))
    )
    (net (code "22") (name "Net-(IC501-QH)") (class "Default")
      (node (ref "IC501") (pin "9") (pinfunction "QH_9") (pintype "output"))
      (node (ref "R501") (pin "1") (pinfunction "P$1_1") (pintype "bidirectional"))
    )
    (net (code "23") (name "Net-(IC501-SER)") (class "Default")
      (node (ref "IC501") (pin "10") (pinfunction "SER_10") (pintype "input"))
      (node (ref "R500") (pin "2") (pinfunction "P$2_2") (pintype "bidirectional"))
    )
    (net (code "24") (name "Net-(IC502-QH)") (class "Default")
      (node (ref "IC502") (pin "9") (pinfunction "QH_9") (pintype "output"))
      (node (ref "R502") (pin "1") (pinfunction "P$1_1") (pintype "bidirectional"))
    )
    (net (code "25") (name "Net-(IC502-SER)") (class "Default")
      (node (ref "IC502") (pin "10") (pinfunction "SER_10") (pintype "input"))
      (node (ref "R501") (pin "2") (pinfunction "P$2_2") (pintype "bidirectional"))
    )
    (net (code "26") (name "Net-(IC503-SER)") (class "Default")
      (node (ref "IC503") (pin "10") (pinfunction "SER_10") (pintype "input"))
      (node (ref "R502") (pin "2") (pinfunction "P$2_2") (pintype "bidirectional"))
    )
    (net (code "27") (name "Net-(J301-1)") (class "Default")
      (node (ref "J301") (pin "P$1") (pinfunction "1_P$1") (pintype "bidirectional"))
      (node (ref "R301") (pin "2") (pinfunction "P$2_2") (pintype "bidirectional"))
    )
    (net (code "28") (name "Net-(J301-3)") (class "Default")
      (node (ref "J301") (pin "P$3") (pinfunction "3_P$3") (pintype "bidirectional"))
      (node (ref "J302") (pin "P$3") (pinfunction "3_P$3") (pintype "bidirectional"))
      (node (ref "R302") (pin "2") (pinfunction "P$2_2") (pintype "bidirectional"))
    )
    (net (code "29") (name "Net-(J302-1)") (class "Default")
      (node (ref "J302") (pin "P$1") (pinfunction "1_P$1") (pintype "bidirectional"))
      (node (ref "R303") (pin "2") (pinfunction "P$2_2") (pintype "bidirectional"))
    )
    (net (code "30") (name "Net-(LED200-A)") (class "Default")
      (node (ref "LED200") (pin "P$2") (pinfunction "A_P$2") (pintype "passive"))
      (node (ref "R200") (pin "1") (pinfunction "P$1_1") (pintype "bidirectional"))
    )
    (net (code "31") (name "Net-(LED300-A)") (class "Default")
      (node (ref "LED300") (pin "P$2") (pinfunction "A_P$2") (pintype "passive"))
      (node (ref "R300") (pin "2") (pinfunction "P$2_2") (pintype "bidirectional"))
    )
    (net (code "32") (name "PED_01") (class "Default")
      (node (ref "IC503") (pin "6") (pinfunction "H_6") (pintype "input"))
      (node (ref "R401") (pin "2") (pinfunction "P$2_2") (pintype "bidirectional"))
      (node (ref "SW401") (pin "2") (pinfunction "2_2") (pintype "bidirectional"))
    )
    (net (code "33") (name "PED_02") (class "Default")
      (node (ref "IC502") (pin "11") (pinfunction "A_11") (pintype "input"))
      (node (ref "R402") (pin "2") (pinfunction "P$2_2") (pintype "bidirectional"))
      (node (ref "SW402") (pin "2") (pinfunction "2_2") (pintype "bidirectional"))
    )
    (net (code "34") (name "PED_03") (class "Default")
      (node (ref "IC502") (pin "12") (pinfunction "B_12") (pintype "input"))
      (node (ref "R403") (pin "2") (pinfunction "P$2_2") (pintype "bidirectional"))
      (node (ref "SW403") (pin "2") (pinfunction "2_2") (pintype "bidirectional"))
    )
    (net (code "35") (name "PED_04") (class "Default")
      (node (ref "IC502") (pin "13") (pinfunction "C_13") (pintype "input"))
      (node (ref "R404") (pin "2") (pinfunction "P$2_2") (pintype "bidirectional"))
      (node (ref "SW404") (pin "2") (pinfunction "2_2") (pintype "bidirectional"))
    )
    (net (code "36") (name "PED_05") (class "Default")
      (node (ref "IC502") (pin "14") (pinfunction "D_14") (pintype "input"))
      (node (ref "R405") (pin "2") (pinfunction "P$2_2") (pintype "bidirectional"))
      (node (ref "SW405") (pin "2") (pinfunction "2_2") (pintype "bidirectional"))
    )
    (net (code "37") (name "PED_06") (class "Default")
      (node (ref "IC502") (pin "3") (pinfunction "E_3") (pintype "input"))
      (node (ref "R406") (pin "2") (pinfunction "P$2_2") (pintype "bidirectional"))
      (node (ref "SW406") (pin "2") (pinfunction "2_2") (pintype "bidirectional"))
    )
    (net (code "38") (name "PED_07") (class "Default")
      (node (ref "IC502") (pin "4") (pinfunction "F_4") (pintype "input"))
      (node (ref "R407") (pin "2") (pinfunction "P$2_2") (pintype "bidirectional"))
      (node (ref "SW407") (pin "2") (pinfunction "2_2") (pintype "bidirectional"))
    )
    (net (code "39") (name "PED_08") (class "Default")
      (node (ref "IC502") (pin "5") (pinfunction "G_5") (pintype "input"))
      (node (ref "R408") (pin "2") (pinfunction "P$2_2") (pintype "bidirectional"))
      (node (ref "SW408") (pin "2") (pinfunction "2_2") (pintype "bidirectional"))
    )
    (net (code "40") (name "PED_09") (class "Default")
      (node (ref "IC502") (pin "6") (pinfunction "H_6") (pintype "input"))
      (node (ref "R409") (pin "2") (pinfunction "P$2_2") (pintype "bidirectional"))
      (node (ref "SW409") (pin "2") (pinfunction "2_2") (pintype "bidirectional"))
    )
    (net (code "41") (name "PED_10") (class "Default")
      (node (ref "IC501") (pin "11") (pinfunction "A_11") (pintype "input"))
      (node (ref "R410") (pin "2") (pinfunction "P$2_2") (pintype "bidirectional"))
      (node (ref "SW410") (pin "2") (pinfunction "2_2") (pintype "bidirectional"))
    )
    (net (code "42") (name "PED_11") (class "Default")
      (node (ref "IC501") (pin "12") (pinfunction "B_12") (pintype "input"))
      (node (ref "R411") (pin "2") (pinfunction "P$2_2") (pintype "bidirectional"))
      (node (ref "SW411") (pin "2") (pinfunction "2_2") (pintype "bidirectional"))
    )
    (net (code "43") (name "PED_12") (class "Default")
      (node (ref "IC501") (pin "13") (pinfunction "C_13") (pintype "input"))
      (node (ref "R412") (pin "2") (pinfunction "P$2_2") (pintype "bidirectional"))
      (node (ref "SW412") (pin "2") (pinfunction "2_2") (pintype "bidirectional"))
    )
    (net (code "44") (name "PED_13") (class "Default")
      (node (ref "IC501") (pin "14") (pinfunction "D_14") (pintype "input"))
      (node (ref "R413") (pin "2") (pinfunction "P$2_2") (pintype "bidirectional"))
      (node (ref "SW413") (pin "2") (pinfunction "2_2") (pintype "bidirectional"))
    )
    (net (code "45") (name "PED_14") (class "Default")
      (node (ref "IC501") (pin "3") (pinfunction "E_3") (pintype "input"))
      (node (ref "R414") (pin "2") (pinfunction "P$2_2") (pintype "bidirectional"))
      (node (ref "SW414") (pin "2") (pinfunction "2_2") (pintype "bidirectional"))
    )
    (net (code "46") (name "PED_15") (class "Default")
      (node (ref "IC501") (pin "4") (pinfunction "F_4") (pintype "input"))
      (node (ref "R415") (pin "2") (pinfunction "P$2_2") (pintype "bidirectional"))
      (node (ref "SW415") (pin "2") (pinfunction "2_2") (pintype "bidirectional"))
    )
    (net (code "47") (name "PED_16") (class "Default")
      (node (ref "IC501") (pin "5") (pinfunction "G_5") (pintype "input"))
      (node (ref "R416") (pin "2") (pinfunction "P$2_2") (pintype "bidirectional"))
      (node (ref "SW416") (pin "2") (pinfunction "2_2") (pintype "bidirectional"))
    )
    (net (code "48") (name "PED_17") (class "Default")
      (node (ref "IC501") (pin "6") (pinfunction "H_6") (pintype "input"))
      (node (ref "R417") (pin "2") (pinfunction "P$2_2") (pintype "bidirectional"))
      (node (ref "SW417") (pin "2") (pinfunction "2_2") (pintype "bidirectional"))
    )
    (net (code "49") (name "PED_18") (class "Default")
      (node (ref "IC500") (pin "11") (pinfunction "A_11") (pintype "input"))
      (node (ref "R418") (pin "2") (pinfunction "P$2_2") (pintype "bidirectional"))
      (node (ref "SW418") (pin "2") (pinfunction "2_2") (pintype "bidirectional"))
    )
    (net (code "50") (name "PED_19") (class "Default")
      (node (ref "IC500") (pin "12") (pinfunction "B_12") (pintype "input"))
      (node (ref "R419") (pin "2") (pinfunction "P$2_2") (pintype "bidirectional"))
      (node (ref "SW419") (pin "2") (pinfunction "2_2") (pintype "bidirectional"))
    )
    (net (code "51") (name "PED_20") (class "Default")
      (node (ref "IC500") (pin "13") (pinfunction "C_13") (pintype "input"))
      (node (ref "R420") (pin "2") (pinfunction "P$2_2") (pintype "bidirectional"))
      (node (ref "SW420") (pin "2") (pinfunction "2_2") (pintype "bidirectional"))
    )
    (net (code "52") (name "PED_21") (class "Default")
      (node (ref "IC500") (pin "14") (pinfunction "D_14") (pintype "input"))
      (node (ref "R421") (pin "2") (pinfunction "P$2_2") (pintype "bidirectional"))
      (node (ref "SW421") (pin "2") (pinfunction "2_2") (pintype "bidirectional"))
    )
    (net (code "53") (name "PED_22") (class "Default")
      (node (ref "IC500") (pin "3") (pinfunction "E_3") (pintype "input"))
      (node (ref "R422") (pin "2") (pinfunction "P$2_2") (pintype "bidirectional"))
      (node (ref "SW422") (pin "2") (pinfunction "2_2") (pintype "bidirectional"))
    )
    (net (code "54") (name "PED_23") (class "Default")
      (node (ref "IC500") (pin "4") (pinfunction "F_4") (pintype "input"))
      (node (ref "R423") (pin "2") (pinfunction "P$2_2") (pintype "bidirectional"))
      (node (ref "SW423") (pin "2") (pinfunction "2_2") (pintype "bidirectional"))
    )
    (net (code "55") (name "PED_24") (class "Default")
      (node (ref "IC500") (pin "5") (pinfunction "G_5") (pintype "input"))
      (node (ref "R424") (pin "2") (pinfunction "P$2_2") (pintype "bidirectional"))
      (node (ref "SW424") (pin "2") (pinfunction "2_2") (pintype "bidirectional"))
    )
    (net (code "56") (name "PED_25") (class "Default")
      (node (ref "IC500") (pin "6") (pinfunction "H_6") (pintype "input"))
      (node (ref "R425") (pin "2") (pinfunction "P$2_2") (pintype "bidirectional"))
      (node (ref "SW425") (pin "2") (pinfunction "2_2") (pintype "bidirectional"))
    )
    (net (code "57") (name "PHOTO_DI_IN") (class "Default")
      (node (ref "J200") (pin "P$2") (pinfunction "2_P$2") (pintype "bidirectional"))
      (node (ref "J201") (pin "P$2") (pinfunction "2_P$2") (pintype "bidirectional"))
    )
    (net (code "58") (name "POLY_MONO") (class "Default")
      (node (ref "IC300") (pin "2") (pinfunction "RA5_2") (pintype "passive"))
      (node (ref "R437") (pin "2") (pinfunction "P$2_2") (pintype "bidirectional"))
      (node (ref "SW400") (pin "P$16") (pinfunction "P$16_P$16") (pintype "bidirectional"))
    )
    (net (code "59") (name "SER_CLK") (class "Default")
      (node (ref "IC500") (pin "2") (pinfunction "CLK_2") (pintype "input"))
      (node (ref "IC501") (pin "2") (pinfunction "CLK_2") (pintype "input"))
      (node (ref "IC502") (pin "2") (pinfunction "CLK_2") (pintype "input"))
      (node (ref "IC503") (pin "2") (pinfunction "CLK_2") (pintype "input"))
      (node (ref "R305") (pin "1") (pinfunction "P$1_1") (pintype "bidirectional"))
    )
    (net (code "60") (name "SER_DATA") (class "Default")
      (node (ref "IC300") (pin "8") (pinfunction "RC2_8") (pintype "passive"))
      (node (ref "IC503") (pin "9") (pinfunction "QH_9") (pintype "output"))
    )
    (net (code "61") (name "SER_SH") (class "Default")
      (node (ref "IC500") (pin "1") (pinfunction "SH/~{LD}_1") (pintype "input"))
      (node (ref "IC501") (pin "1") (pinfunction "SH/~{LD}_1") (pintype "input"))
      (node (ref "IC502") (pin "1") (pinfunction "SH/~{LD}_1") (pintype "input"))
      (node (ref "IC503") (pin "1") (pinfunction "SH/~{LD}_1") (pintype "input"))
      (node (ref "R304") (pin "1") (pinfunction "P$1_1") (pintype "bidirectional"))
    )
    (net (code "62") (name "VPP") (class "Default")
      (node (ref "IC300") (pin "4") (pinfunction "VPP_RA3_4") (pintype "passive"))
      (node (ref "J300") (pin "P$1") (pinfunction "1_P$1") (pintype "bidirectional"))
    )
    (net (code "63") (name "unconnected-(IC300-RA2-Pad11)") (class "Default")
      (node (ref "IC300") (pin "11") (pinfunction "RA2_11") (pintype "passive"))
    )
    (net (code "64") (name "unconnected-(IC300-RA4-Pad3)") (class "Default")
      (node (ref "IC300") (pin "3") (pinfunction "RA4_3") (pintype "passive"))
    )
    (net (code "65") (name "unconnected-(IC300-RC5_RX-Pad5)") (class "Default")
      (node (ref "IC300") (pin "5") (pinfunction "RC5_RX_5") (pintype "passive"))
    )
    (net (code "66") (name "unconnected-(IC500-~{QH}-Pad7)") (class "Default")
      (node (ref "IC500") (pin "7") (pinfunction "~{QH}_7") (pintype "output"))
    )
    (net (code "67") (name "unconnected-(IC501-~{QH}-Pad7)") (class "Default")
      (node (ref "IC501") (pin "7") (pinfunction "~{QH}_7") (pintype "output"))
    )
    (net (code "68") (name "unconnected-(IC502-~{QH}-Pad7)") (class "Default")
      (node (ref "IC502") (pin "7") (pinfunction "~{QH}_7") (pintype "output"))
    )
    (net (code "69") (name "unconnected-(IC503-~{QH}-Pad7)") (class "Default")
      (node (ref "IC503") (pin "7") (pinfunction "~{QH}_7") (pintype "output"))
    )
    (net (code "70") (name "unconnected-(J200-9-PadP$9)") (class "Default")
      (node (ref "J200") (pin "P$9") (pinfunction "9_P$9") (pintype "bidirectional"))
    )
    (net (code "71") (name "unconnected-(J200-10-PadP$10)") (class "Default")
      (node (ref "J200") (pin "P$10") (pinfunction "10_P$10") (pintype "bidirectional"))
    )
    (net (code "72") (name "unconnected-(J201-9-PadP$9)") (class "Default")
      (node (ref "J201") (pin "P$9") (pinfunction "9_P$9") (pintype "bidirectional"))
    )
    (net (code "73") (name "unconnected-(J201-10-PadP$10)") (class "Default")
      (node (ref "J201") (pin "P$10") (pinfunction "10_P$10") (pintype "bidirectional"))
    )
    (net (code "74") (name "unconnected-(J300-6-PadP$6)") (class "Default")
      (node (ref "J300") (pin "P$6") (pinfunction "6_P$6") (pintype "bidirectional"))
    )
  )
)
